# Sheet1.net
KiCad netlist of a schematic drawn in Altium Designer
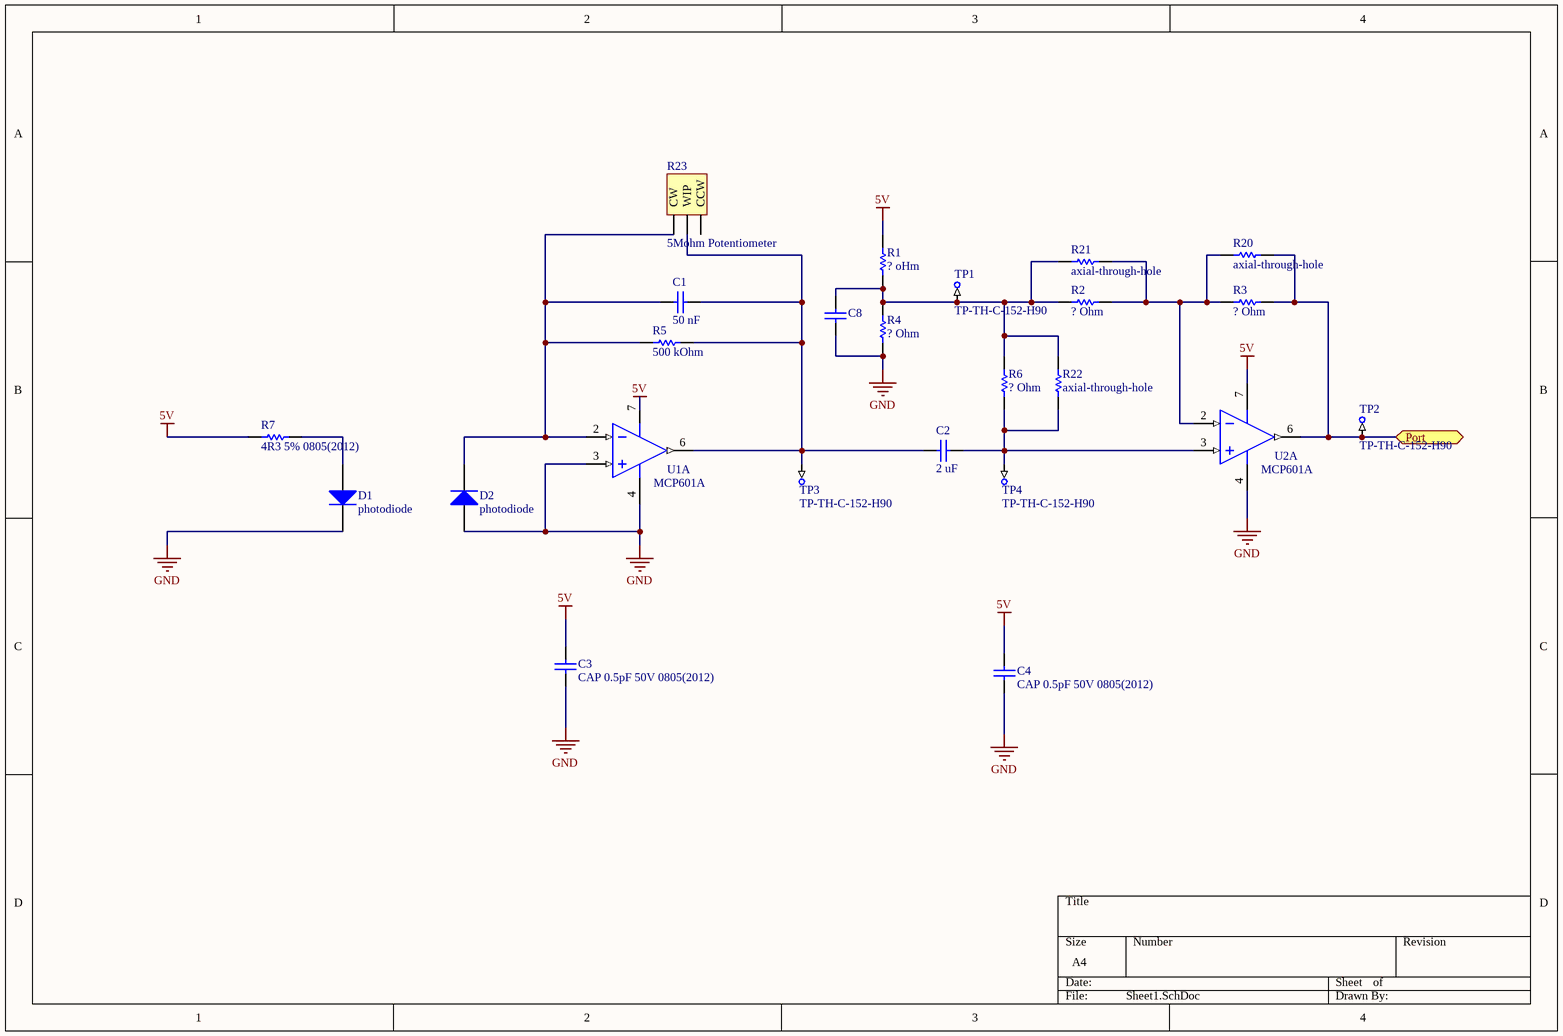
[diagram p0: Sheet1.SchDoc]

(export (version "E")
  (design (tool "Eeschema 10.0.6"))
  (components
    (comp (ref "C1")
      (value "50 nF")
      (footprint "CAPC0805(2012)75_M")
      (description "CAP 0.5pF 50V ±0.1pF 0805 (2012 Metric) Thickness 0.75mm SMD")
      (fields (field (name "TOLERANCE") "Â±0.1pF"))
      (libsource (lib "Altium Content Vault") (part "CMP-1036-00018-1"))
    )
    (comp (ref "C2")
      (value "2 uF")
      (footprint "CAPC0805(2012)75_M")
      (description "CAP 0.5pF 50V ±0.1pF 0805 (2012 Metric) Thickness 0.75mm SMD")
      (fields (field (name "TOLERANCE") "Â±0.1pF"))
      (libsource (lib "Altium Content Vault") (part "CMP-1036-00018-1"))
    )
    (comp (ref "C3")
      (value "CAP 0.5pF 50V 0805(2012)")
      (footprint "CAPC0805(2012)75_M")
      (description "CAP 0.5pF 50V ±0.1pF 0805 (2012 Metric) Thickness 0.75mm SMD")
      (fields (field (name "TOLERANCE") "Â±0.1pF"))
      (libsource (lib "Altium Content Vault") (part "CAP"))
    )
    (comp (ref "C4")
      (value "CAP 0.5pF 50V 0805(2012)")
      (footprint "CAPC0805(2012)75_M")
      (description "CAP 0.5pF 50V ±0.1pF 0805 (2012 Metric) Thickness 0.75mm SMD")
      (fields (field (name "TOLERANCE") "Â±0.1pF"))
      (libsource (lib "Altium Content Vault") (part "CAP"))
    )
    (comp (ref "C8")
      (value "CAP 0.5pF 50V 0805(2012)")
      (footprint "CAPC0805(2012)75_M")
      (description "CAP 0.5pF 50V ±0.1pF 0805 (2012 Metric) Thickness 0.75mm SMD")
      (fields (field (name "TOLERANCE") "Â±0.1pF"))
      (libsource (lib "Altium Content Vault") (part "CMP-1036-00018-1"))
    )
    (comp (ref "D1")
      (value "photodiode")
      (footprint "3mm_diode")
      (libsource (lib "HeartbeatLibrary") (part "photodiode"))
    )
    (comp (ref "D2")
      (value "photodiode")
      (footprint "3mm_diode")
      (libsource (lib "HeartbeatLibrary") (part "photodiode"))
    )
    (comp (ref "R1")
      (value "? oHm")
      (footprint "RESC0805(2012)_M")
      (description "4R3 0.125W 5% 0805 (2012 Metric)  SMD")
      (fields (field (name "TOLERANCE") "5 %") (field (name "POWER") "0.125 W"))
      (libsource (lib "Altium Content Vault") (part "RES"))
    )
    (comp (ref "R2")
      (value "? Ohm")
      (footprint "RESC0805(2012)_M")
      (description "4R3 0.125W 5% 0805 (2012 Metric)  SMD")
      (fields (field (name "TOLERANCE") "5 %") (field (name "POWER") "0.125 W"))
      (libsource (lib "Altium Content Vault") (part "RES"))
    )
    (comp (ref "R3")
      (value "? Ohm")
      (footprint "RESC0805(2012)_M")
      (description "4R3 0.125W 5% 0805 (2012 Metric)  SMD")
      (fields (field (name "TOLERANCE") "5 %") (field (name "POWER") "0.125 W"))
      (libsource (lib "Altium Content Vault") (part "CMP-1013-00017-1"))
    )
    (comp (ref "R4")
      (value "? Ohm")
      (footprint "RESC0805(2012)_M")
      (description "4R3 0.125W 5% 0805 (2012 Metric)  SMD")
      (fields (field (name "TOLERANCE") "5 %") (field (name "POWER") "0.125 W"))
      (libsource (lib "Altium Content Vault") (part "RES"))
    )
    (comp (ref "R5")
      (value "500 kOhm")
      (footprint "RESC0805(2012)_M")
      (description "4R3 0.125W 5% 0805 (2012 Metric)  SMD")
      (fields (field (name "TOLERANCE") "5 %") (field (name "POWER") "0.125 W"))
      (libsource (lib "Altium Content Vault") (part "CMP-1013-00017-1"))
    )
    (comp (ref "R6")
      (value "? Ohm")
      (footprint "RESC0805(2012)_M")
      (description "4R3 0.125W 5% 0805 (2012 Metric)  SMD")
      (fields (field (name "TOLERANCE") "5 %") (field (name "POWER") "0.125 W"))
      (libsource (lib "Altium Content Vault") (part "RES"))
    )
    (comp (ref "R7")
      (value "4R3 5% 0805(2012)")
      (footprint "RESC0805(2012)_M")
      (description "4R3 0.125W 5% 0805 (2012 Metric)  SMD")
      (fields (field (name "TOLERANCE") "5 %") (field (name "POWER") "0.125 W"))
      (libsource (lib "Altium Content Vault") (part "RES"))
    )
    (comp (ref "R20")
      (value "axial-through-hole")
      (footprint "Axial_resistor")
      (description "through-hole")
      (libsource (lib "HeartbeatLibrary") (part "axial-through-hole"))
    )
    (comp (ref "R21")
      (value "axial-through-hole")
      (footprint "Axial_resistor")
      (description "through-hole")
      (libsource (lib "HeartbeatLibrary") (part "axial-through-hole"))
    )
    (comp (ref "R22")
      (value "axial-through-hole")
      (footprint "Axial_resistor")
      (description "through-hole")
      (libsource (lib "HeartbeatLibrary") (part "axial-through-hole"))
    )
    (comp (ref "R23")
      (value "5Mohm Potentiometer")
      (footprint "5k_pot")
      (description "3296W-1-505LF")
      (libsource (lib "HeartbeatLibrary") (part "5Mohm Potentiometer"))
    )
    (comp (ref "TP1")
      (value "TP-TH-C-152-H90")
      (footprint "TP-TH-C-152-H90")
      (description "Test Point, Through Hole, Hole Size 0.9 mm, PCB Mount with Silkscreen Box")
      (fields (field (name "MANUFACTURER") "No Vendor"))
      (libsource (lib "Altium Content Vault") (part "TP-TH"))
    )
    (comp (ref "TP2")
      (value "TP-TH-C-152-H90")
      (footprint "TP-TH-C-152-H90")
      (description "Test Point, Through Hole, Hole Size 0.9 mm, PCB Mount with Silkscreen Box")
      (fields (field (name "MANUFACTURER") "No Vendor"))
      (libsource (lib "Altium Content Vault") (part "TP-TH"))
    )
    (comp (ref "TP3")
      (value "TP-TH-C-152-H90")
      (footprint "TP-TH-C-152-H90")
      (description "Test Point, Through Hole, Hole Size 0.9 mm, PCB Mount with Silkscreen Box")
      (fields (field (name "MANUFACTURER") "No Vendor"))
      (libsource (lib "Altium Content Vault") (part "TP-TH"))
    )
    (comp (ref "TP4")
      (value "TP-TH-C-152-H90")
      (footprint "TP-TH-C-152-H90")
      (description "Test Point, Through Hole, Hole Size 0.9 mm, PCB Mount with Silkscreen Box")
      (fields (field (name "MANUFACTURER") "No Vendor"))
      (libsource (lib "Altium Content Vault") (part "TP-TH"))
    )
    (comp (ref "U1")
      (value "MCP601A")
      (footprint "ADI-Q-8")
      (fields
        (field (name "MANUFACTURER") "Analog Devices")
        (field (name "PARTNUMBER") "5962-9459301MPA")
        (field (name "GENERIC PART NUMBER") "AD8001")
      )
      (libsource (lib "Altium Content Vault") (part "ADI-AD_ADA_OPXXXX-X-8"))
    )
    (comp (ref "U2")
      (value "MCP601A")
      (footprint "ADI-Q-8")
      (fields
        (field (name "MANUFACTURER") "Analog Devices")
        (field (name "PARTNUMBER") "5962-9459301MPA")
        (field (name "GENERIC PART NUMBER") "AD8001")
      )
      (libsource (lib "Altium Content Vault") (part "ADI-AD_ADA_OPXXXX-X-8"))
    )
  )
  (nets
    (net (code "1") (name "/Port") (class "Default")
      (node (ref "R20") (pin "2") (pinfunction "2_2") (pintype "passive"))
      (node (ref "R3") (pin "2") (pinfunction "2_2") (pintype "passive"))
      (node (ref "TP2") (pin "1") (pinfunction "1_1") (pintype "input"))
      (node (ref "U2") (pin "6") (pinfunction "OUT_6") (pintype "output"))
    )
    (net (code "2") (name "5V") (class "Default")
      (node (ref "C3") (pin "2") (pinfunction "2_2") (pintype "passive"))
      (node (ref "C4") (pin "2") (pinfunction "2_2") (pintype "passive"))
      (node (ref "R1") (pin "2") (pinfunction "2_2") (pintype "passive"))
      (node (ref "R7") (pin "2") (pinfunction "2_2") (pintype "passive"))
      (node (ref "U1") (pin "7") (pinfunction "+V_7") (pintype "power_in"))
      (node (ref "U2") (pin "7") (pinfunction "+V_7") (pintype "power_in"))
    )
    (net (code "3") (name "GND") (class "Default")
      (node (ref "C3") (pin "1") (pinfunction "1_1") (pintype "passive"))
      (node (ref "C4") (pin "1") (pinfunction "1_1") (pintype "passive"))
      (node (ref "C8") (pin "1") (pinfunction "1_1") (pintype "passive"))
      (node (ref "D1") (pin "2") (pinfunction "K_2") (pintype "passive"))
      (node (ref "D2") (pin "1") (pinfunction "A_1") (pintype "passive"))
      (node (ref "R4") (pin "1") (pinfunction "1_1") (pintype "passive"))
      (node (ref "U1") (pin "3") (pinfunction "+IN_3") (pintype "input"))
      (node (ref "U1") (pin "4") (pinfunction "-V_4") (pintype "power_in"))
      (node (ref "U2") (pin "4") (pinfunction "-V_4") (pintype "power_in"))
    )
    (net (code "4") (name "Net-(C8-Pad2)") (class "Default")
      (node (ref "C8") (pin "2") (pinfunction "2_2") (pintype "passive"))
      (node (ref "R1") (pin "1") (pinfunction "1_1") (pintype "passive"))
      (node (ref "R2") (pin "1") (pinfunction "1_1") (pintype "passive"))
      (node (ref "R21") (pin "1") (pinfunction "1_1") (pintype "passive"))
      (node (ref "R22") (pin "2") (pinfunction "2_2") (pintype "passive"))
      (node (ref "R4") (pin "2") (pinfunction "2_2") (pintype "passive"))
      (node (ref "R6") (pin "2") (pinfunction "2_2") (pintype "passive"))
      (node (ref "TP1") (pin "1") (pinfunction "1_1") (pintype "input"))
    )
    (net (code "5") (name "Net-(D1-A)") (class "Default")
      (node (ref "D1") (pin "1") (pinfunction "A_1") (pintype "passive"))
      (node (ref "R7") (pin "1") (pinfunction "1_1") (pintype "passive"))
    )
    (net (code "6") (name "Net-(D2-K)") (class "Default")
      (node (ref "C1") (pin "2") (pinfunction "2_2") (pintype "passive"))
      (node (ref "D2") (pin "2") (pinfunction "K_2") (pintype "passive"))
      (node (ref "R23") (pin "1") (pinfunction "CW_1") (pintype "passive"))
      (node (ref "R5") (pin "1") (pinfunction "1_1") (pintype "passive"))
      (node (ref "U1") (pin "2") (pinfunction "-IN_2") (pintype "input"))
    )
    (net (code "7") (name "Net-(R23-WIP)") (class "Default")
      (node (ref "C1") (pin "1") (pinfunction "1_1") (pintype "passive"))
      (node (ref "C2") (pin "2") (pinfunction "2_2") (pintype "passive"))
      (node (ref "R23") (pin "2") (pinfunction "WIP_2") (pintype "passive"))
      (node (ref "R5") (pin "2") (pinfunction "2_2") (pintype "passive"))
      (node (ref "TP3") (pin "1") (pinfunction "1_1") (pintype "input"))
      (node (ref "U1") (pin "6") (pinfunction "OUT_6") (pintype "output"))
    )
    (net (code "8") (name "Net-(U2A-+IN)") (class "Default")
      (node (ref "C2") (pin "1") (pinfunction "1_1") (pintype "passive"))
      (node (ref "R22") (pin "1") (pinfunction "1_1") (pintype "passive"))
      (node (ref "R6") (pin "1") (pinfunction "1_1") (pintype "passive"))
      (node (ref "TP4") (pin "1") (pinfunction "1_1") (pintype "input"))
      (node (ref "U2") (pin "3") (pinfunction "+IN_3") (pintype "input"))
    )
    (net (code "9") (name "Net-(U2A--IN)") (class "Default")
      (node (ref "R2") (pin "2") (pinfunction "2_2") (pintype "passive"))
      (node (ref "R20") (pin "1") (pinfunction "1_1") (pintype "passive"))
      (node (ref "R21") (pin "2") (pinfunction "2_2") (pintype "passive"))
      (node (ref "R3") (pin "1") (pinfunction "1_1") (pintype "passive"))
      (node (ref "U2") (pin "2") (pinfunction "-IN_2") (pintype "input"))
    )
    (net (code "10") (name "unconnected-(R23-CCW-Pad3)") (class "Default")
      (node (ref "R23") (pin "3") (pinfunction "CCW_3") (pintype "passive"))
    )
  )
)
